# Supply_DDS.net
KiCad netlist of a schematic drawn in Altium Designer
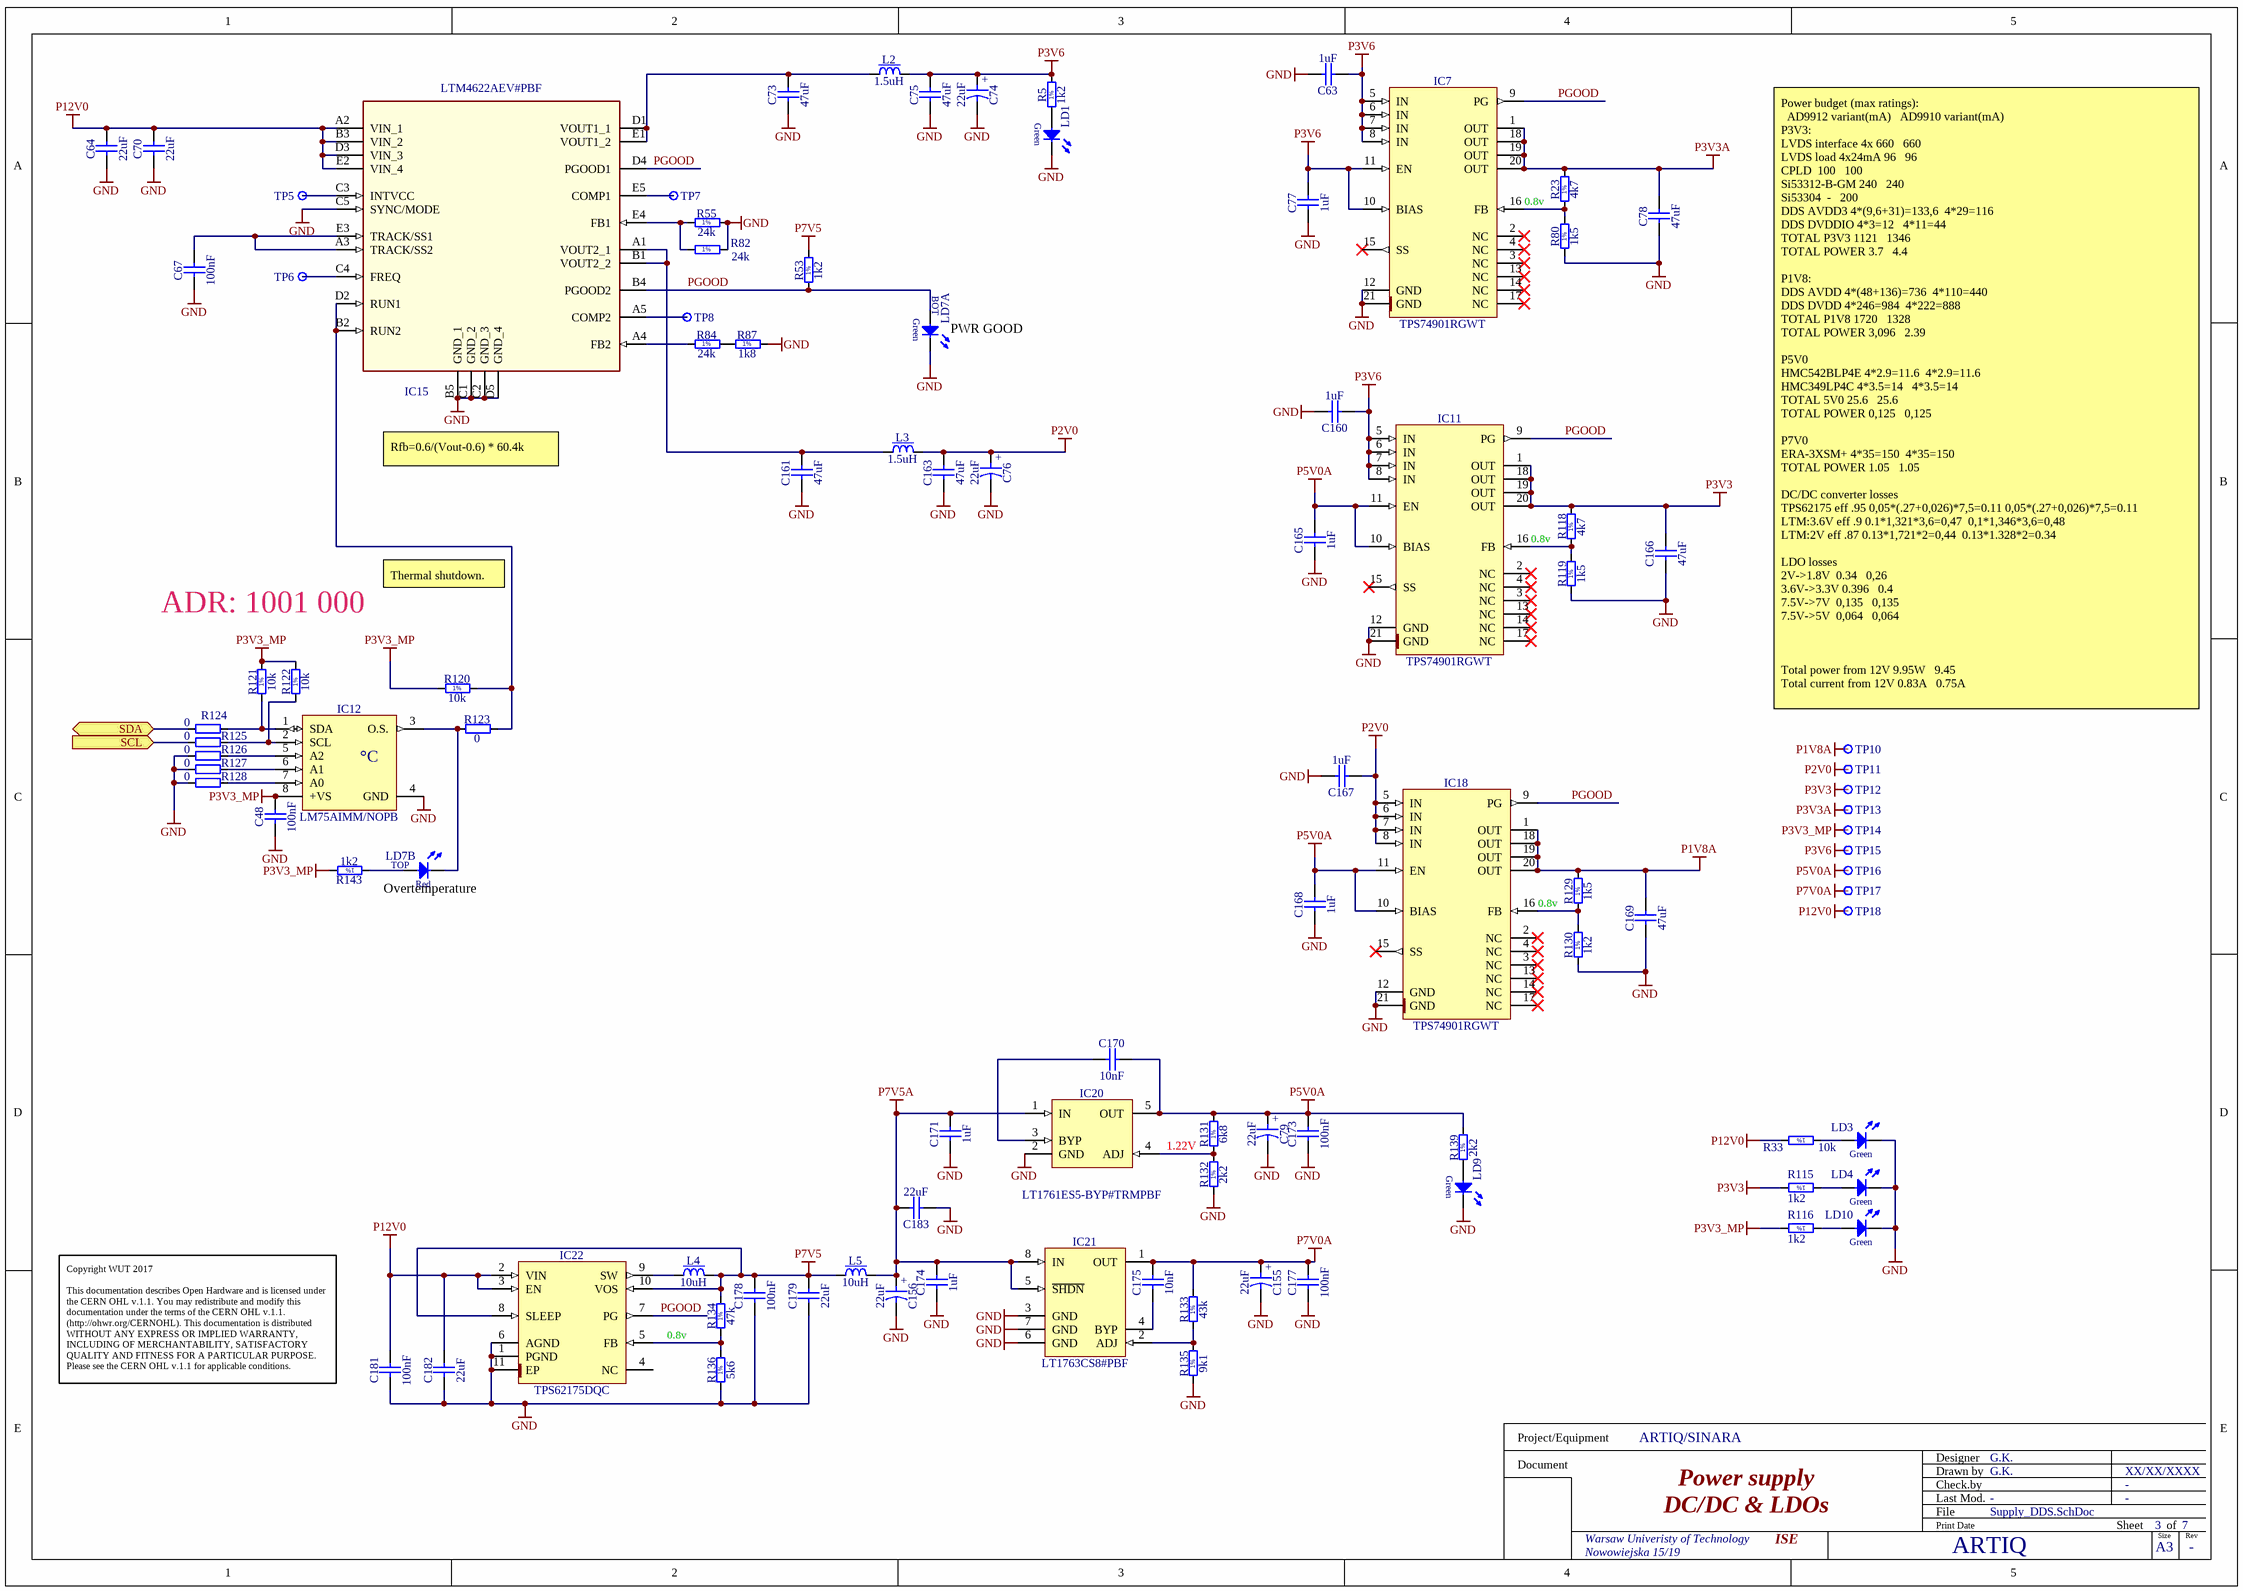
[diagram p0: Supply_DDS.SchDoc]

(export (version "E")
  (design (tool "Eeschema 10.0.6"))
  (components
    (comp (ref "C48")
      (value "100nF")
      (footprint "CAPC1005X55N")
      (description "Non-polarised capacitor")
      (fields (field (name "PART NUMBER") "CC0402_100NF_16V_10%_X5R") (field (name "VOLTAGE") "16V"))
      (libsource (lib "Capacitors") (part "Capacitor - non polarized"))
    )
    (comp (ref "C63")
      (value "1uF")
      (footprint "CAPC1005X55N")
      (description "Non-polarised capacitor")
      (fields (field (name "PART NUMBER") "CC0402_1UF_16V_10%_X5R") (field (name "VOLTAGE") "16V"))
      (libsource (lib "Capacitors") (part "Capacitor - non polarized"))
    )
    (comp (ref "C64")
      (value "22uF")
      (footprint "CAPC2012X135N")
      (description "Non-polarised capacitor")
      (fields (field (name "PART NUMBER") "CC0805_22UF_16V_10%_X5R") (field (name "VOLTAGE") "16V"))
      (libsource (lib "Capacitors") (part "Capacitor - non polarized"))
    )
    (comp (ref "C67")
      (value "100nF")
      (footprint "CAPC1005X55N")
      (description "Non-polarised capacitor")
      (fields (field (name "PART NUMBER") "CC0402_100NF_16V_10%_X5R") (field (name "VOLTAGE") "16V"))
      (libsource (lib "Capacitors") (part "Capacitor - non polarized"))
    )
    (comp (ref "C70")
      (value "22uF")
      (footprint "CAPC2012X135N")
      (description "Non-polarised capacitor")
      (fields (field (name "PART NUMBER") "CC0805_22UF_16V_10%_X5R") (field (name "VOLTAGE") "16V"))
      (libsource (lib "Capacitors") (part "Capacitor - non polarized"))
    )
    (comp (ref "C73")
      (value "47uF")
      (footprint "CAPC3225X270N")
      (description "Non-polarised capacitor")
      (fields (field (name "PART NUMBER") "CC1210_47UF_10V_20%_X5R") (field (name "VOLTAGE") "10V"))
      (libsource (lib "Capacitors") (part "Capacitor - non polarized"))
    )
    (comp (ref "C74")
      (value "22uF")
      (footprint "CAPMP3528X210N")
      (description "Polarised capacitor")
      (fields (field (name "PART NUMBER") "CTE3528-21_22UF_10V_10%_LESR0700") (field (name "VOLTAGE") "10V"))
      (libsource (lib "Capacitors") (part "Capacitor - polarized"))
    )
    (comp (ref "C75")
      (value "47uF")
      (footprint "CAPC3225X270N")
      (description "Non-polarised capacitor")
      (fields (field (name "PART NUMBER") "CC1210_47UF_10V_20%_X5R") (field (name "VOLTAGE") "10V"))
      (libsource (lib "Capacitors") (part "Capacitor - non polarized"))
    )
    (comp (ref "C76")
      (value "22uF")
      (footprint "CAPMP3528X210N")
      (description "Polarised capacitor")
      (fields (field (name "PART NUMBER") "CTE3528-21_22UF_10V_10%_LESR0700") (field (name "VOLTAGE") "10V"))
      (libsource (lib "Capacitors") (part "Capacitor - polarized"))
    )
    (comp (ref "C77")
      (value "1uF")
      (footprint "CAPC1005X55N")
      (description "Non-polarised capacitor")
      (fields (field (name "PART NUMBER") "CC0402_1UF_16V_10%_X5R") (field (name "VOLTAGE") "16V"))
      (libsource (lib "Capacitors") (part "Capacitor - non polarized"))
    )
    (comp (ref "C78")
      (value "47uF")
      (footprint "CAPC3225X270N")
      (description "Non-polarised capacitor")
      (fields (field (name "PART NUMBER") "CC1210_47UF_10V_20%_X5R") (field (name "VOLTAGE") "10V"))
      (libsource (lib "Capacitors") (part "Capacitor - non polarized"))
    )
    (comp (ref "C79")
      (value "22uF")
      (footprint "CAPMP3528X210N")
      (description "Polarised capacitor")
      (fields (field (name "PART NUMBER") "CTE3528-21_22UF_10V_10%_LESR0700") (field (name "VOLTAGE") "10V"))
      (libsource (lib "Capacitors") (part "Capacitor - polarized"))
    )
    (comp (ref "C155")
      (value "22uF")
      (footprint "CAPMP3528X210N")
      (description "Polarised capacitor")
      (fields (field (name "PART NUMBER") "CTE3528-21_22UF_10V_10%_LESR0700") (field (name "VOLTAGE") "10V"))
      (libsource (lib "Capacitors") (part "Capacitor - polarized"))
    )
    (comp (ref "C156")
      (value "22uF")
      (footprint "CAPMP3528X210N")
      (description "Polarised capacitor")
      (fields (field (name "PART NUMBER") "CTE3528-21_22UF_10V_10%_LESR0700") (field (name "VOLTAGE") "10V"))
      (libsource (lib "Capacitors") (part "Capacitor - polarized"))
    )
    (comp (ref "C160")
      (value "1uF")
      (footprint "CAPC1005X55N")
      (description "Non-polarised capacitor")
      (fields (field (name "PART NUMBER") "CC0402_1UF_16V_10%_X5R") (field (name "VOLTAGE") "16V"))
      (libsource (lib "Capacitors") (part "Capacitor - non polarized"))
    )
    (comp (ref "C161")
      (value "47uF")
      (footprint "CAPC3225X270N")
      (description "Non-polarised capacitor")
      (fields (field (name "PART NUMBER") "CC1210_47UF_10V_20%_X5R") (field (name "VOLTAGE") "10V"))
      (libsource (lib "Capacitors") (part "Capacitor - non polarized"))
    )
    (comp (ref "C163")
      (value "47uF")
      (footprint "CAPC3225X270N")
      (description "Non-polarised capacitor")
      (fields (field (name "PART NUMBER") "CC1210_47UF_10V_20%_X5R") (field (name "VOLTAGE") "10V"))
      (libsource (lib "Capacitors") (part "Capacitor - non polarized"))
    )
    (comp (ref "C165")
      (value "1uF")
      (footprint "CAPC1005X55N")
      (description "Non-polarised capacitor")
      (fields (field (name "PART NUMBER") "CC0402_1UF_16V_10%_X5R") (field (name "VOLTAGE") "16V"))
      (libsource (lib "Capacitors") (part "Capacitor - non polarized"))
    )
    (comp (ref "C166")
      (value "47uF")
      (footprint "CAPC3225X270N")
      (description "Non-polarised capacitor")
      (fields (field (name "PART NUMBER") "CC1210_47UF_10V_20%_X5R") (field (name "VOLTAGE") "10V"))
      (libsource (lib "Capacitors") (part "Capacitor - non polarized"))
    )
    (comp (ref "C167")
      (value "1uF")
      (footprint "CAPC1005X55N")
      (description "Non-polarised capacitor")
      (fields (field (name "PART NUMBER") "CC0402_1UF_16V_10%_X5R") (field (name "VOLTAGE") "16V"))
      (libsource (lib "Capacitors") (part "Capacitor - non polarized"))
    )
    (comp (ref "C168")
      (value "1uF")
      (footprint "CAPC1005X55N")
      (description "Non-polarised capacitor")
      (fields (field (name "PART NUMBER") "CC0402_1UF_16V_10%_X5R") (field (name "VOLTAGE") "16V"))
      (libsource (lib "Capacitors") (part "Capacitor - non polarized"))
    )
    (comp (ref "C169")
      (value "47uF")
      (footprint "CAPC3225X270N")
      (description "Non-polarised capacitor")
      (fields (field (name "PART NUMBER") "CC1210_47UF_10V_20%_X5R") (field (name "VOLTAGE") "10V"))
      (libsource (lib "Capacitors") (part "Capacitor - non polarized"))
    )
    (comp (ref "C170")
      (value "10nF")
      (footprint "CAPC1005X55N")
      (description "Non-polarised capacitor")
      (fields (field (name "PART NUMBER") "CC0402_10NF_16V_10%_X7R") (field (name "VOLTAGE") "16V"))
      (libsource (lib "Capacitors") (part "Capacitor - non polarized"))
    )
    (comp (ref "C171")
      (value "1uF")
      (footprint "CAPC1005X55N")
      (description "Non-polarised capacitor")
      (fields (field (name "PART NUMBER") "CC0402_1UF_16V_10%_X5R") (field (name "VOLTAGE") "16V"))
      (libsource (lib "Capacitors") (part "Capacitor - non polarized"))
    )
    (comp (ref "C173")
      (value "100nF")
      (footprint "CAPC1005X55N")
      (description "Non-polarised capacitor")
      (fields (field (name "PART NUMBER") "CC0402_100NF_16V_10%_X5R") (field (name "VOLTAGE") "16V"))
      (libsource (lib "Capacitors") (part "Capacitor - non polarized"))
    )
    (comp (ref "C174")
      (value "1uF")
      (footprint "CAPC1005X55N")
      (description "Non-polarised capacitor")
      (fields (field (name "PART NUMBER") "CC0402_1UF_16V_10%_X5R") (field (name "VOLTAGE") "16V"))
      (libsource (lib "Capacitors") (part "Capacitor - non polarized"))
    )
    (comp (ref "C175")
      (value "10nF")
      (footprint "CAPC1005X55N")
      (description "Non-polarised capacitor")
      (fields (field (name "PART NUMBER") "CC0402_10NF_16V_10%_X7R") (field (name "VOLTAGE") "16V"))
      (libsource (lib "Capacitors") (part "Capacitor - non polarized"))
    )
    (comp (ref "C177")
      (value "100nF")
      (footprint "CAPC1005X55N")
      (description "Non-polarised capacitor")
      (fields (field (name "PART NUMBER") "CC0402_100NF_16V_10%_X5R") (field (name "VOLTAGE") "16V"))
      (libsource (lib "Capacitors") (part "Capacitor - non polarized"))
    )
    (comp (ref "C178")
      (value "100nF")
      (footprint "CAPC1005X55N")
      (description "Non-polarised capacitor")
      (fields (field (name "PART NUMBER") "CC0402_100NF_16V_10%_X5R") (field (name "VOLTAGE") "16V"))
      (libsource (lib "Capacitors") (part "Capacitor - non polarized"))
    )
    (comp (ref "C179")
      (value "22uF")
      (footprint "CAPC2012X135N")
      (description "Non-polarised capacitor")
      (fields (field (name "PART NUMBER") "CC0805_22UF_16V_10%_X5R") (field (name "VOLTAGE") "16V"))
      (libsource (lib "Capacitors") (part "Capacitor - non polarized"))
    )
    (comp (ref "C181")
      (value "100nF")
      (footprint "CAPC1005X55N")
      (description "Non-polarised capacitor")
      (fields (field (name "PART NUMBER") "CC0402_100NF_16V_10%_X5R") (field (name "VOLTAGE") "16V"))
      (libsource (lib "Capacitors") (part "Capacitor - non polarized"))
    )
    (comp (ref "C182")
      (value "22uF")
      (footprint "CAPC2012X135N")
      (description "Non-polarised capacitor")
      (fields (field (name "PART NUMBER") "CC0805_22UF_16V_10%_X5R") (field (name "VOLTAGE") "16V"))
      (libsource (lib "Capacitors") (part "Capacitor - non polarized"))
    )
    (comp (ref "C183")
      (value "22uF")
      (footprint "CAPC2012X135N")
      (description "Non-polarised capacitor")
      (fields (field (name "PART NUMBER") "CC0805_22UF_16V_10%_X5R") (field (name "VOLTAGE") "16V"))
      (libsource (lib "Capacitors") (part "Capacitor - non polarized"))
    )
    (comp (ref "IC7")
      (value "TPS74901RGWT")
      (footprint "QFN65P500X500X100-21N-S325")
      (description "3A, 0.8 to 3.6V Adjustable Low-Dropout Linear Regulator with Programmable Soft-Start")
      (fields (field (name "MANUFACTURER") "TEXAS INSTRUMENTS"))
      (libsource (lib "ICs And Semiconductors") (part "TPS74901RGWT"))
    )
    (comp (ref "IC11")
      (value "TPS74901RGWT")
      (footprint "QFN65P500X500X100-21N-S325")
      (description "3A, 0.8 to 3.6V Adjustable Low-Dropout Linear Regulator with Programmable Soft-Start")
      (fields (field (name "MANUFACTURER") "TEXAS INSTRUMENTS"))
      (libsource (lib "ICs And Semiconductors") (part "TPS74901RGWT"))
    )
    (comp (ref "IC12")
      (value "LM75AIMM/NOPB")
      (footprint "SOP65P490X109-8N")
      (description "Digital Temperature Sensor and Thermal Watchdog with Two-Wire Interface")
      (fields (field (name "MANUFACTURER") "TEXAS INSTRUMENTS"))
      (libsource (lib "ICs And Semiconductors") (part "LM75"))
    )
    (comp (ref "IC15")
      (value "LTM4622AEV#PBF")
      (footprint "LGA25C127P5X5_625X625X190")
      (description "Dual Ultrathin 2A or Single 4A, 3.6V to 20V, 1.5V to 12V   Step-Down DC/DC μModule Regulator")
      (fields (field (name "MANUFACTURER") "LINEAR TECHNOLOGY"))
      (libsource (lib "LIBRARY_SCH") (part "PM_LTM4622"))
    )
    (comp (ref "IC18")
      (value "TPS74901RGWT")
      (footprint "QFN65P500X500X100-21N-S325")
      (description "3A, 0.8 to 3.6V Adjustable Low-Dropout Linear Regulator with Programmable Soft-Start")
      (fields (field (name "MANUFACTURER") "TEXAS INSTRUMENTS"))
      (libsource (lib "ICs And Semiconductors") (part "TPS74901RGWT"))
    )
    (comp (ref "IC20")
      (value "LT1761ES5-BYP#TRMPBF")
      (footprint "SOT95P280X100-5N")
      (description "100mA, Low Noise, LDO Micropower Adjustable Regulator in SOT-23")
      (fields (field (name "MANUFACTURER") "LINEAR TECHNOLOGY"))
      (libsource (lib "ICs And Semiconductors") (part "LT1761-BYP"))
    )
    (comp (ref "IC21")
      (value "LT1763CS8#PBF")
      (footprint "SOIC127P600X175-8N")
      (description "1.22V to 20V 500mA, Low Noise, LDO Adjustable Micropower Regulator")
      (fields (field (name "MANUFACTURER") "LINEAR TECHNOLOGY"))
      (libsource (lib "ICs And Semiconductors") (part "LT1763xS8"))
    )
    (comp (ref "IC22")
      (value "TPS62175DQC")
      (footprint "SON50P200X300X80-11N-R94X250")
      (description "4.75-28VDC to 1-6VDC, 500mA Step-Down Converter With Sleep Mode")
      (fields (field (name "MANUFACTURER") "TEXAS INSTRUMENTS"))
      (libsource (lib "ICs And Semiconductors") (part "TPS62175"))
    )
    (comp (ref "L2")
      (value "1.5uH")
      (footprint "IND_TDK_SPM6530")
      (description "Inductor With Core")
      (fields (field (name "PART NUMBER") "IND_1.5UH_20%_TDK_SPM6530") (field (name "POWER") "11A"))
      (libsource (lib "Inductors & Transformers") (part "Inductor With Magnetic core"))
    )
    (comp (ref "L3")
      (value "1.5uH")
      (footprint "IND_TDK_SPM6530")
      (description "Inductor With Core")
      (fields (field (name "PART NUMBER") "IND_1.5UH_20%_TDK_SPM6530") (field (name "POWER") "11A"))
      (libsource (lib "Inductors & Transformers") (part "Inductor With Magnetic core"))
    )
    (comp (ref "L4")
      (value "10uH")
      (footprint "IND_MURATA-PS_8400")
      (description "Inductor With Core")
      (fields (field (name "PART NUMBER") "IND_10UH_10%_MURATA-PS_8400") (field (name "POWER") "950mA"))
      (libsource (lib "Inductors & Transformers") (part "Inductor With Magnetic core"))
    )
    (comp (ref "L5")
      (value "10uH")
      (footprint "IND_MURATA-PS_8400")
      (description "Inductor With Core")
      (fields (field (name "PART NUMBER") "IND_10UH_10%_MURATA-PS_8400") (field (name "POWER") "950mA"))
      (libsource (lib "Inductors & Transformers") (part "Inductor With Magnetic core"))
    )
    (comp (ref "LD1")
      (value "Green")
      (footprint "LED_KINGBRIGHT_KPH-1608CGCKr")
      (description "Green 0603")
      (fields
        (field (name "PART NUMBER") "LED_KINGBRIGHT_KPH-1608CGCK")
        (field (name "MANUFACTURER") "KINGBRIGHT")
      )
      (libsource (lib "LIBRARY_SCH") (part "LED_0603_Green"))
    )
    (comp (ref "LD3")
      (value "Green")
      (footprint "LED_KINGBRIGHT_KPH-1608CGCKr")
      (description "Green 0603")
      (fields
        (field (name "PART NUMBER") "LED_KINGBRIGHT_KPH-1608CGCK")
        (field (name "MANUFACTURER") "KINGBRIGHT")
      )
      (libsource (lib "LIBRARY_SCH") (part "LED_0603_Green"))
    )
    (comp (ref "LD4")
      (value "Green")
      (footprint "LED_KINGBRIGHT_KPH-1608CGCKr")
      (description "Green 0603")
      (fields
        (field (name "PART NUMBER") "LED_KINGBRIGHT_KPH-1608CGCK")
        (field (name "MANUFACTURER") "KINGBRIGHT")
      )
      (libsource (lib "LIBRARY_SCH") (part "LED_0603_Green"))
    )
    (comp (ref "LD7")
      (value "Red/Green")
      (footprint "LED_DIALIGHT_553-0112-200F")
      (description "2x LED  Botom Green, Top Red")
      (fields
        (field (name "PART NUMBER") "LED_DIALIGHT_553-0112-200F")
        (field (name "MANUFACTURER") "DIALIGHT")
      )
      (libsource (lib "ICs And Semiconductors") (part "LED x2 G-1C2A-BOT_R-3C4A-TOP"))
    )
    (comp (ref "LD9")
      (value "Green")
      (footprint "LED_KINGBRIGHT_KPH-1608CGCKr")
      (description "Green 0603")
      (fields
        (field (name "PART NUMBER") "LED_KINGBRIGHT_KPH-1608CGCK")
        (field (name "MANUFACTURER") "KINGBRIGHT")
      )
      (libsource (lib "LIBRARY_SCH") (part "LED_0603_Green"))
    )
    (comp (ref "LD10")
      (value "Green")
      (footprint "LED_KINGBRIGHT_KPH-1608CGCKr")
      (description "Green 0603")
      (fields
        (field (name "PART NUMBER") "LED_KINGBRIGHT_KPH-1608CGCK")
        (field (name "MANUFACTURER") "KINGBRIGHT")
      )
      (libsource (lib "LIBRARY_SCH") (part "LED_0603_Green"))
    )
    (comp (ref "R5")
      (value "1k2")
      (footprint "RESC1608X55N")
      (description "Resistor - 1%")
      (fields (field (name "PART NUMBER") "R0603_1K2_1%_0.1W_100PPM") (field (name "POWER") "0.1W"))
      (libsource (lib "Resistors") (part "Resistor - 1%"))
    )
    (comp (ref "R23")
      (value "4k7")
      (footprint "RESC1608X55N")
      (description "Resistor - 1%")
      (fields (field (name "PART NUMBER") "R0603_4K7_1%_0.1W_100PPM") (field (name "POWER") "0.1W"))
      (libsource (lib "Resistors") (part "Resistor - 1%"))
    )
    (comp (ref "R33")
      (value "10k")
      (footprint "RESC1005X40N")
      (description "Resistor - 1%")
      (fields (field (name "PART NUMBER") "R0402_10K_1%_0.0625W_100PPM") (field (name "POWER") "0.0625W"))
      (libsource (lib "Resistors") (part "Resistor - 1%"))
    )
    (comp (ref "R53")
      (value "1k2")
      (footprint "RESC1608X55N")
      (description "Resistor - 1%")
      (fields (field (name "PART NUMBER") "R0603_1K2_1%_0.1W_100PPM") (field (name "POWER") "0.1W"))
      (libsource (lib "Resistors") (part "Resistor - 1%"))
    )
    (comp (ref "R55")
      (value "24k")
      (footprint "RESC1608X55N")
      (description "Resistor - 1%")
      (fields (field (name "PART NUMBER") "R0603_24K_1%_0.1W_100PPM") (field (name "POWER") "0.1W"))
      (libsource (lib "Resistors") (part "Resistor - 1%"))
    )
    (comp (ref "R80")
      (value "1k5")
      (footprint "RESC1608X55N")
      (description "Resistor - 1%")
      (fields (field (name "PART NUMBER") "R0603_1K5_1%_0.1W_100PPM") (field (name "POWER") "0.1W"))
      (libsource (lib "Resistors") (part "Resistor - 1%"))
    )
    (comp (ref "R82")
      (value "24k")
      (footprint "RESC1608X55N")
      (description "Resistor - 1%")
      (fields (field (name "PART NUMBER") "R0603_24K_1%_0.1W_100PPM") (field (name "POWER") "0.1W"))
      (libsource (lib "Resistors") (part "Resistor - 1%"))
    )
    (comp (ref "R84")
      (value "24k")
      (footprint "RESC1608X55N")
      (description "Resistor - 1%")
      (fields (field (name "PART NUMBER") "R0603_24K_1%_0.1W_100PPM") (field (name "POWER") "0.1W"))
      (libsource (lib "Resistors") (part "Resistor - 1%"))
    )
    (comp (ref "R87")
      (value "1k8")
      (footprint "RESC1608X55N")
      (description "Resistor - 1%")
      (fields (field (name "PART NUMBER") "R0603_1K8_1%_0.1W_100PPM") (field (name "POWER") "0.1W"))
      (libsource (lib "Resistors") (part "Resistor - 1%"))
    )
    (comp (ref "R115")
      (value "1k2")
      (footprint "RESC1608X55N")
      (description "Resistor - 1%")
      (fields (field (name "PART NUMBER") "R0603_1K2_1%_0.1W_100PPM") (field (name "POWER") "0.1W"))
      (libsource (lib "Resistors") (part "Resistor - 1%"))
    )
    (comp (ref "R116")
      (value "1k2")
      (footprint "RESC1608X55N")
      (description "Resistor - 1%")
      (fields (field (name "PART NUMBER") "R0603_1K2_1%_0.1W_100PPM") (field (name "POWER") "0.1W"))
      (libsource (lib "Resistors") (part "Resistor - 1%"))
    )
    (comp (ref "R118")
      (value "4k7")
      (footprint "RESC1608X55N")
      (description "Resistor - 1%")
      (fields (field (name "PART NUMBER") "R0603_4K7_1%_0.1W_100PPM") (field (name "POWER") "0.1W"))
      (libsource (lib "Resistors") (part "Resistor - 1%"))
    )
    (comp (ref "R119")
      (value "1k5")
      (footprint "RESC1608X55N")
      (description "Resistor - 1%")
      (fields (field (name "PART NUMBER") "R0603_1K5_1%_0.1W_100PPM") (field (name "POWER") "0.1W"))
      (libsource (lib "Resistors") (part "Resistor - 1%"))
    )
    (comp (ref "R120")
      (value "10k")
      (footprint "RESC1005X40N")
      (description "Resistor - 1%")
      (fields (field (name "PART NUMBER") "R0402_10K_1%_0.0625W_100PPM") (field (name "POWER") "0.0625W"))
      (libsource (lib "Resistors") (part "Resistor - 1%"))
    )
    (comp (ref "R121")
      (value "10k")
      (footprint "RESC1005X40N")
      (description "Resistor - 1%")
      (fields (field (name "PART NUMBER") "R0402_10K_1%_0.0625W_100PPM") (field (name "POWER") "0.0625W"))
      (libsource (lib "Resistors") (part "Resistor - 1%"))
    )
    (comp (ref "R122")
      (value "10k")
      (footprint "RESC1005X40N")
      (description "Resistor - 1%")
      (fields (field (name "PART NUMBER") "R0402_10K_1%_0.0625W_100PPM") (field (name "POWER") "0.0625W"))
      (libsource (lib "Resistors") (part "Resistor - 1%"))
    )
    (comp (ref "R123")
      (value "0")
      (footprint "RESC1005X40N")
      (description "Resistor")
      (fields (field (name "PART NUMBER") "R0402_0R_JUMPER") (field (name "MANUFACTURER") "GENERIC"))
      (libsource (lib "Resistors") (part "Resistor"))
    )
    (comp (ref "R124")
      (value "0")
      (footprint "RESC1005X40N")
      (description "Resistor")
      (fields (field (name "PART NUMBER") "R0402_0R_JUMPER") (field (name "MANUFACTURER") "GENERIC"))
      (libsource (lib "Resistors") (part "Resistor"))
    )
    (comp (ref "R125")
      (value "0")
      (footprint "RESC1005X40N")
      (description "Resistor")
      (fields (field (name "PART NUMBER") "R0402_0R_JUMPER") (field (name "MANUFACTURER") "GENERIC"))
      (libsource (lib "Resistors") (part "Resistor"))
    )
    (comp (ref "R126")
      (value "0")
      (footprint "RESC1005X40N")
      (description "Resistor")
      (fields (field (name "PART NUMBER") "R0402_0R_JUMPER") (field (name "MANUFACTURER") "GENERIC"))
      (libsource (lib "Resistors") (part "Resistor"))
    )
    (comp (ref "R127")
      (value "0")
      (footprint "RESC1005X40N")
      (description "Resistor")
      (fields (field (name "PART NUMBER") "R0402_0R_JUMPER") (field (name "MANUFACTURER") "GENERIC"))
      (libsource (lib "Resistors") (part "Resistor"))
    )
    (comp (ref "R128")
      (value "0")
      (footprint "RESC1005X40N")
      (description "Resistor")
      (fields (field (name "PART NUMBER") "R0402_0R_JUMPER") (field (name "MANUFACTURER") "GENERIC"))
      (libsource (lib "Resistors") (part "Resistor"))
    )
    (comp (ref "R129")
      (value "1k5")
      (footprint "RESC1608X55N")
      (description "Resistor - 1%")
      (fields (field (name "PART NUMBER") "R0603_1K5_1%_0.1W_100PPM") (field (name "POWER") "0.1W"))
      (libsource (lib "Resistors") (part "Resistor - 1%"))
    )
    (comp (ref "R130")
      (value "1k2")
      (footprint "RESC1608X55N")
      (description "Resistor - 1%")
      (fields (field (name "PART NUMBER") "R0603_1K2_1%_0.1W_100PPM") (field (name "POWER") "0.1W"))
      (libsource (lib "Resistors") (part "Resistor - 1%"))
    )
    (comp (ref "R131")
      (value "6k8")
      (footprint "RESC1608X55N")
      (description "Resistor - 1%")
      (fields (field (name "PART NUMBER") "R0603_6K8_1%_0.1W_100PPM") (field (name "POWER") "0.1W"))
      (libsource (lib "Resistors") (part "Resistor - 1%"))
    )
    (comp (ref "R132")
      (value "2k2")
      (footprint "RESC1608X55N")
      (description "Resistor - 1%")
      (fields (field (name "PART NUMBER") "R0603_2K2_1%_0.1W_100PPM") (field (name "POWER") "0.1W"))
      (libsource (lib "Resistors") (part "Resistor - 1%"))
    )
    (comp (ref "R133")
      (value "43k")
      (footprint "RESC1608X55N")
      (description "Resistor - 1%")
      (fields (field (name "PART NUMBER") "R0603_43K_1%_0.1W_100PPM") (field (name "POWER") "0.1W"))
      (libsource (lib "Resistors") (part "Resistor - 1%"))
    )
    (comp (ref "R134")
      (value "47k")
      (footprint "RESC1608X55N")
      (description "Resistor - 1%")
      (fields (field (name "PART NUMBER") "R0603_47K_1%_0.1W_100PPM") (field (name "POWER") "0.1W"))
      (libsource (lib "Resistors") (part "Resistor - 1%"))
    )
    (comp (ref "R135")
      (value "9k1")
      (footprint "RESC1608X55N")
      (description "Resistor - 1%")
      (fields (field (name "PART NUMBER") "R0603_9K1_1%_0.1W_100PPM") (field (name "POWER") "0.1W"))
      (libsource (lib "Resistors") (part "Resistor - 1%"))
    )
    (comp (ref "R136")
      (value "5k6")
      (footprint "RESC1608X55N")
      (description "Resistor - 1%")
      (fields (field (name "PART NUMBER") "R0603_5K6_1%_0.1W_100PPM") (field (name "POWER") "0.1W"))
      (libsource (lib "Resistors") (part "Resistor - 1%"))
    )
    (comp (ref "R139")
      (value "2k2")
      (footprint "RESC1608X55N")
      (description "Resistor - 1%")
      (fields (field (name "PART NUMBER") "R0603_2K2_1%_0.1W_100PPM") (field (name "POWER") "0.1W"))
      (libsource (lib "Resistors") (part "Resistor - 1%"))
    )
    (comp (ref "R143")
      (value "1k2")
      (footprint "RESC1608X55N")
      (description "Resistor - 1%")
      (fields (field (name "PART NUMBER") "R0603_1K2_1%_0.1W_100PPM") (field (name "POWER") "0.1W"))
      (libsource (lib "Resistors") (part "Resistor - 1%"))
    )
    (comp (ref "TP5")
      (value "Test Point")
      (footprint "TPS127")
      (fields (field (name "PART NUMBER") "SMD_PAD_1.27X1.27MM"))
      (libsource (lib "Eletro-mechanical") (part "Test Point"))
    )
    (comp (ref "TP6")
      (value "Test Point")
      (footprint "TPS127")
      (fields (field (name "PART NUMBER") "SMD_PAD_1.27X1.27MM"))
      (libsource (lib "Eletro-mechanical") (part "Test Point"))
    )
    (comp (ref "TP7")
      (value "Test Point")
      (footprint "TPS127")
      (fields (field (name "PART NUMBER") "SMD_PAD_1.27X1.27MM"))
      (libsource (lib "Eletro-mechanical") (part "Test Point"))
    )
    (comp (ref "TP8")
      (value "Test Point")
      (footprint "TPS127")
      (fields (field (name "PART NUMBER") "SMD_PAD_1.27X1.27MM"))
      (libsource (lib "Eletro-mechanical") (part "Test Point"))
    )
    (comp (ref "TP10")
      (value "Test Point")
      (footprint "TPS127")
      (fields (field (name "PART NUMBER") "SMD_PAD_1.27X1.27MM"))
      (libsource (lib "Eletro-mechanical") (part "Test Point"))
    )
    (comp (ref "TP11")
      (value "Test Point")
      (footprint "TPS127")
      (fields (field (name "PART NUMBER") "SMD_PAD_1.27X1.27MM"))
      (libsource (lib "Eletro-mechanical") (part "Test Point"))
    )
    (comp (ref "TP12")
      (value "Test Point")
      (footprint "TPS127")
      (fields (field (name "PART NUMBER") "SMD_PAD_1.27X1.27MM"))
      (libsource (lib "Eletro-mechanical") (part "Test Point"))
    )
    (comp (ref "TP13")
      (value "Test Point")
      (footprint "TPS127")
      (fields (field (name "PART NUMBER") "SMD_PAD_1.27X1.27MM"))
      (libsource (lib "Eletro-mechanical") (part "Test Point"))
    )
    (comp (ref "TP14")
      (value "Test Point")
      (footprint "TPS127")
      (fields (field (name "PART NUMBER") "SMD_PAD_1.27X1.27MM"))
      (libsource (lib "Eletro-mechanical") (part "Test Point"))
    )
    (comp (ref "TP15")
      (value "Test Point")
      (footprint "TPS127")
      (fields (field (name "PART NUMBER") "SMD_PAD_1.27X1.27MM"))
      (libsource (lib "Eletro-mechanical") (part "Test Point"))
    )
    (comp (ref "TP16")
      (value "Test Point")
      (footprint "TPS127")
      (fields (field (name "PART NUMBER") "SMD_PAD_1.27X1.27MM"))
      (libsource (lib "Eletro-mechanical") (part "Test Point"))
    )
    (comp (ref "TP17")
      (value "Test Point")
      (footprint "TPS127")
      (fields (field (name "PART NUMBER") "SMD_PAD_1.27X1.27MM"))
      (libsource (lib "Eletro-mechanical") (part "Test Point"))
    )
    (comp (ref "TP18")
      (value "Test Point")
      (footprint "TPS127")
      (fields (field (name "PART NUMBER") "SMD_PAD_1.27X1.27MM"))
      (libsource (lib "Eletro-mechanical") (part "Test Point"))
    )
  )
  (nets
    (net (code "1") (name "/PGOOD") (class "Default")
      (node (ref "IC11") (pin "9") (pinfunction "PG_9") (pintype "output"))
      (node (ref "IC15") (pin "B4") (pinfunction "PGOOD2_B4") (pintype "open_collector"))
      (node (ref "IC15") (pin "D4") (pinfunction "PGOOD1_D4") (pintype "open_collector"))
      (node (ref "IC18") (pin "9") (pinfunction "PG_9") (pintype "output"))
      (node (ref "IC22") (pin "7") (pinfunction "PG_7") (pintype "output"))
      (node (ref "IC7") (pin "9") (pinfunction "PG_9") (pintype "output"))
      (node (ref "LD7") (pin "2") (pinfunction "A_2") (pintype "passive"))
      (node (ref "R53") (pin "1") (pinfunction "1_1") (pintype "passive"))
    )
    (net (code "2") (name "/SCL") (class "Default")
      (node (ref "R125") (pin "1") (pinfunction "1_1") (pintype "passive"))
    )
    (net (code "3") (name "/SDA") (class "Default")
      (node (ref "R124") (pin "1") (pinfunction "1_1") (pintype "passive"))
    )
    (net (code "4") (name "GND") (class "Default")
      (node (ref "C155") (pin "2") (pinfunction "2_2") (pintype "passive"))
      (node (ref "C156") (pin "2") (pinfunction "2_2") (pintype "passive"))
      (node (ref "C160") (pin "2") (pinfunction "2_2") (pintype "passive"))
      (node (ref "C161") (pin "1") (pinfunction "1_1") (pintype "passive"))
      (node (ref "C163") (pin "1") (pinfunction "1_1") (pintype "passive"))
      (node (ref "C165") (pin "1") (pinfunction "1_1") (pintype "passive"))
      (node (ref "C166") (pin "1") (pinfunction "1_1") (pintype "passive"))
      (node (ref "C167") (pin "2") (pinfunction "2_2") (pintype "passive"))
      (node (ref "C168") (pin "1") (pinfunction "1_1") (pintype "passive"))
      (node (ref "C169") (pin "1") (pinfunction "1_1") (pintype "passive"))
      (node (ref "C171") (pin "1") (pinfunction "1_1") (pintype "passive"))
      (node (ref "C173") (pin "1") (pinfunction "1_1") (pintype "passive"))
      (node (ref "C174") (pin "1") (pinfunction "1_1") (pintype "passive"))
      (node (ref "C177") (pin "1") (pinfunction "1_1") (pintype "passive"))
      (node (ref "C178") (pin "1") (pinfunction "1_1") (pintype "passive"))
      (node (ref "C179") (pin "1") (pinfunction "1_1") (pintype "passive"))
      (node (ref "C181") (pin "1") (pinfunction "1_1") (pintype "passive"))
      (node (ref "C182") (pin "1") (pinfunction "1_1") (pintype "passive"))
      (node (ref "C183") (pin "1") (pinfunction "1_1") (pintype "passive"))
      (node (ref "C48") (pin "1") (pinfunction "1_1") (pintype "passive"))
      (node (ref "C63") (pin "2") (pinfunction "2_2") (pintype "passive"))
      (node (ref "C64") (pin "1") (pinfunction "1_1") (pintype "passive"))
      (node (ref "C67") (pin "1") (pinfunction "1_1") (pintype "passive"))
      (node (ref "C70") (pin "1") (pinfunction "1_1") (pintype "passive"))
      (node (ref "C73") (pin "1") (pinfunction "1_1") (pintype "passive"))
      (node (ref "C74") (pin "2") (pinfunction "2_2") (pintype "passive"))
      (node (ref "C75") (pin "1") (pinfunction "1_1") (pintype "passive"))
      (node (ref "C76") (pin "2") (pinfunction "2_2") (pintype "passive"))
      (node (ref "C77") (pin "1") (pinfunction "1_1") (pintype "passive"))
      (node (ref "C78") (pin "1") (pinfunction "1_1") (pintype "passive"))
      (node (ref "C79") (pin "2") (pinfunction "2_2") (pintype "passive"))
      (node (ref "IC11") (pin "12") (pinfunction "GND_12") (pintype "power_in"))
      (node (ref "IC11") (pin "21") (pinfunction "GND_21") (pintype "power_in"))
      (node (ref "IC12") (pin "4") (pinfunction "GND_4") (pintype "power_in"))
      (node (ref "IC15") (pin "B5") (pinfunction "GND_1_B5") (pintype "power_in"))
      (node (ref "IC15") (pin "C1") (pinfunction "GND_2_C1") (pintype "power_in"))
      (node (ref "IC15") (pin "C2") (pinfunction "GND_3_C2") (pintype "power_in"))
      (node (ref "IC15") (pin "C5") (pinfunction "SYNC/MODE_C5") (pintype "input"))
      (node (ref "IC15") (pin "D5") (pinfunction "GND_4_D5") (pintype "power_in"))
      (node (ref "IC18") (pin "12") (pinfunction "GND_12") (pintype "power_in"))
      (node (ref "IC18") (pin "21") (pinfunction "GND_21") (pintype "power_in"))
      (node (ref "IC20") (pin "2") (pinfunction "GND_2") (pintype "power_in"))
      (node (ref "IC21") (pin "3") (pinfunction "GND_3") (pintype "power_in"))
      (node (ref "IC21") (pin "6") (pinfunction "GND_6") (pintype "power_in"))
      (node (ref "IC21") (pin "7") (pinfunction "GND_7") (pintype "power_in"))
      (node (ref "IC22") (pin "1") (pinfunction "PGND_1") (pintype "power_in"))
      (node (ref "IC22") (pin "11") (pinfunction "EP_11") (pintype "power_in"))
      (node (ref "IC22") (pin "6") (pinfunction "AGND_6") (pintype "power_in"))
      (node (ref "IC7") (pin "12") (pinfunction "GND_12") (pintype "power_in"))
      (node (ref "IC7") (pin "21") (pinfunction "GND_21") (pintype "power_in"))
      (node (ref "LD1") (pin "1") (pinfunction "C_1") (pintype "passive"))
      (node (ref "LD10") (pin "1") (pinfunction "C_1") (pintype "passive"))
      (node (ref "LD3") (pin "1") (pinfunction "C_1") (pintype "passive"))
      (node (ref "LD4") (pin "1") (pinfunction "C_1") (pintype "passive"))
      (node (ref "LD7") (pin "1") (pinfunction "C_1") (pintype "passive"))
      (node (ref "LD9") (pin "1") (pinfunction "C_1") (pintype "passive"))
      (node (ref "R119") (pin "1") (pinfunction "1_1") (pintype "passive"))
      (node (ref "R126") (pin "1") (pinfunction "1_1") (pintype "passive"))
      (node (ref "R127") (pin "1") (pinfunction "1_1") (pintype "passive"))
      (node (ref "R128") (pin "1") (pinfunction "1_1") (pintype "passive"))
      (node (ref "R130") (pin "1") (pinfunction "1_1") (pintype "passive"))
      (node (ref "R132") (pin "1") (pinfunction "1_1") (pintype "passive"))
      (node (ref "R135") (pin "1") (pinfunction "1_1") (pintype "passive"))
      (node (ref "R136") (pin "1") (pinfunction "1_1") (pintype "passive"))
      (node (ref "R55") (pin "2") (pinfunction "2_2") (pintype "passive"))
      (node (ref "R80") (pin "1") (pinfunction "1_1") (pintype "passive"))
      (node (ref "R82") (pin "2") (pinfunction "2_2") (pintype "passive"))
      (node (ref "R87") (pin "2") (pinfunction "2_2") (pintype "passive"))
    )
    (net (code "5") (name "Net-(IC7-FB)") (class "Default")
      (node (ref "IC7") (pin "16") (pinfunction "FB_16") (pintype "input"))
      (node (ref "R23") (pin "1") (pinfunction "1_1") (pintype "passive"))
      (node (ref "R80") (pin "2") (pinfunction "2_2") (pintype "passive"))
    )
    (net (code "6") (name "Net-(IC11-FB)") (class "Default")
      (node (ref "IC11") (pin "16") (pinfunction "FB_16") (pintype "input"))
      (node (ref "R118") (pin "1") (pinfunction "1_1") (pintype "passive"))
      (node (ref "R119") (pin "2") (pinfunction "2_2") (pintype "passive"))
    )
    (net (code "7") (name "Net-(IC12-A0)") (class "Default")
      (node (ref "IC12") (pin "7") (pinfunction "A0_7") (pintype "input"))
      (node (ref "R128") (pin "2") (pinfunction "2_2") (pintype "passive"))
    )
    (net (code "8") (name "Net-(IC12-A1)") (class "Default")
      (node (ref "IC12") (pin "6") (pinfunction "A1_6") (pintype "input"))
      (node (ref "R127") (pin "2") (pinfunction "2_2") (pintype "passive"))
    )
    (net (code "9") (name "Net-(IC12-A2)") (class "Default")
      (node (ref "IC12") (pin "5") (pinfunction "A2_5") (pintype "input"))
      (node (ref "R126") (pin "2") (pinfunction "2_2") (pintype "passive"))
    )
    (net (code "10") (name "Net-(IC12-O.S.)") (class "Default")
      (node (ref "IC12") (pin "3") (pinfunction "O.S._3") (pintype "output"))
      (node (ref "LD7") (pin "3") (pinfunction "C_3") (pintype "passive"))
      (node (ref "R123") (pin "1") (pinfunction "1_1") (pintype "passive"))
    )
    (net (code "11") (name "Net-(IC12-SCL)") (class "Default")
      (node (ref "IC12") (pin "2") (pinfunction "SCL_2") (pintype "input"))
      (node (ref "R122") (pin "1") (pinfunction "1_1") (pintype "passive"))
      (node (ref "R125") (pin "2") (pinfunction "2_2") (pintype "passive"))
    )
    (net (code "12") (name "Net-(IC12-SDA)") (class "Default")
      (node (ref "IC12") (pin "1") (pinfunction "SDA_1") (pintype "bidirectional"))
      (node (ref "R121") (pin "1") (pinfunction "1_1") (pintype "passive"))
      (node (ref "R124") (pin "2") (pinfunction "2_2") (pintype "passive"))
    )
    (net (code "13") (name "Net-(IC15-COMP1)") (class "Default")
      (node (ref "IC15") (pin "E5") (pinfunction "COMP1_E5") (pintype "passive"))
      (node (ref "TP7") (pin "1") (pinfunction "1_1") (pintype "bidirectional"))
    )
    (net (code "14") (name "Net-(IC15-COMP2)") (class "Default")
      (node (ref "IC15") (pin "A5") (pinfunction "COMP2_A5") (pintype "passive"))
      (node (ref "TP8") (pin "1") (pinfunction "1_1") (pintype "bidirectional"))
    )
    (net (code "15") (name "Net-(IC15-FB1)") (class "Default")
      (node (ref "IC15") (pin "E4") (pinfunction "FB1_E4") (pintype "input"))
      (node (ref "R55") (pin "1") (pinfunction "1_1") (pintype "passive"))
      (node (ref "R82") (pin "1") (pinfunction "1_1") (pintype "passive"))
    )
    (net (code "16") (name "Net-(IC15-FB2)") (class "Default")
      (node (ref "IC15") (pin "A4") (pinfunction "FB2_A4") (pintype "input"))
      (node (ref "R84") (pin "1") (pinfunction "1_1") (pintype "passive"))
    )
    (net (code "17") (name "Net-(IC15-FREQ)") (class "Default")
      (node (ref "IC15") (pin "C4") (pinfunction "FREQ_C4") (pintype "input"))
      (node (ref "TP6") (pin "1") (pinfunction "1_1") (pintype "bidirectional"))
    )
    (net (code "18") (name "Net-(IC15-INTVCC)") (class "Default")
      (node (ref "IC15") (pin "C3") (pinfunction "INTVCC_C3") (pintype "input"))
      (node (ref "TP5") (pin "1") (pinfunction "1_1") (pintype "bidirectional"))
    )
    (net (code "19") (name "Net-(IC15-RUN1)") (class "Default")
      (node (ref "IC15") (pin "B2") (pinfunction "RUN2_B2") (pintype "input"))
      (node (ref "IC15") (pin "D2") (pinfunction "RUN1_D2") (pintype "input"))
      (node (ref "R120") (pin "2") (pinfunction "2_2") (pintype "passive"))
      (node (ref "R123") (pin "2") (pinfunction "2_2") (pintype "passive"))
    )
    (net (code "20") (name "Net-(IC15-TRACK{slash}SS1)") (class "Default")
      (node (ref "C67") (pin "2") (pinfunction "2_2") (pintype "passive"))
      (node (ref "IC15") (pin "A3") (pinfunction "TRACK/SS2_A3") (pintype "input"))
      (node (ref "IC15") (pin "E3") (pinfunction "TRACK/SS1_E3") (pintype "input"))
    )
    (net (code "21") (name "Net-(IC15-VOUT1_1)") (class "Default")
      (node (ref "C73") (pin "2") (pinfunction "2_2") (pintype "passive"))
      (node (ref "IC15") (pin "D1") (pinfunction "VOUT1_1_D1") (pintype "power_in"))
      (node (ref "IC15") (pin "E1") (pinfunction "VOUT1_2_E1") (pintype "power_in"))
      (node (ref "L2") (pin "1") (pinfunction "1_1") (pintype "passive"))
    )
    (net (code "22") (name "Net-(IC15-VOUT2_1)") (class "Default")
      (node (ref "C161") (pin "2") (pinfunction "2_2") (pintype "passive"))
      (node (ref "IC15") (pin "A1") (pinfunction "VOUT2_1_A1") (pintype "power_in"))
      (node (ref "IC15") (pin "B1") (pinfunction "VOUT2_2_B1") (pintype "power_in"))
      (node (ref "L3") (pin "1") (pinfunction "1_1") (pintype "passive"))
    )
    (net (code "23") (name "Net-(IC18-FB)") (class "Default")
      (node (ref "IC18") (pin "16") (pinfunction "FB_16") (pintype "input"))
      (node (ref "R129") (pin "1") (pinfunction "1_1") (pintype "passive"))
      (node (ref "R130") (pin "2") (pinfunction "2_2") (pintype "passive"))
    )
    (net (code "24") (name "Net-(IC20-ADJ)") (class "Default")
      (node (ref "IC20") (pin "4") (pinfunction "ADJ_4") (pintype "input"))
      (node (ref "R131") (pin "1") (pinfunction "1_1") (pintype "passive"))
      (node (ref "R132") (pin "2") (pinfunction "2_2") (pintype "passive"))
    )
    (net (code "25") (name "Net-(IC20-BYP)") (class "Default")
      (node (ref "C170") (pin "1") (pinfunction "1_1") (pintype "passive"))
      (node (ref "IC20") (pin "3") (pinfunction "BYP_3") (pintype "input"))
    )
    (net (code "26") (name "Net-(IC21-ADJ)") (class "Default")
      (node (ref "IC21") (pin "2") (pinfunction "ADJ_2") (pintype "input"))
      (node (ref "R133") (pin "1") (pinfunction "1_1") (pintype "passive"))
      (node (ref "R135") (pin "2") (pinfunction "2_2") (pintype "passive"))
    )
    (net (code "27") (name "Net-(IC21-BYP)") (class "Default")
      (node (ref "C175") (pin "1") (pinfunction "1_1") (pintype "passive"))
      (node (ref "IC21") (pin "4") (pinfunction "BYP_4") (pintype "passive"))
    )
    (net (code "28") (name "Net-(IC22-FB)") (class "Default")
      (node (ref "IC22") (pin "5") (pinfunction "FB_5") (pintype "input"))
      (node (ref "R134") (pin "1") (pinfunction "1_1") (pintype "passive"))
      (node (ref "R136") (pin "2") (pinfunction "2_2") (pintype "passive"))
    )
    (net (code "29") (name "Net-(IC22-SW)") (class "Default")
      (node (ref "IC22") (pin "9") (pinfunction "SW_9") (pintype "output"))
      (node (ref "L4") (pin "1") (pinfunction "1_1") (pintype "passive"))
    )
    (net (code "30") (name "Net-(LD1-A)") (class "Default")
      (node (ref "LD1") (pin "2") (pinfunction "A_2") (pintype "passive"))
      (node (ref "R5") (pin "1") (pinfunction "1_1") (pintype "passive"))
    )
    (net (code "31") (name "Net-(LD3-A)") (class "Default")
      (node (ref "LD3") (pin "2") (pinfunction "A_2") (pintype "passive"))
      (node (ref "R33") (pin "1") (pinfunction "1_1") (pintype "passive"))
    )
    (net (code "32") (name "Net-(LD4-A)") (class "Default")
      (node (ref "LD4") (pin "2") (pinfunction "A_2") (pintype "passive"))
      (node (ref "R115") (pin "1") (pinfunction "1_1") (pintype "passive"))
    )
    (net (code "33") (name "Net-(LD7B-A)") (class "Default")
      (node (ref "LD7") (pin "4") (pinfunction "A_4") (pintype "passive"))
      (node (ref "R143") (pin "1") (pinfunction "1_1") (pintype "passive"))
    )
    (net (code "34") (name "Net-(LD9-A)") (class "Default")
      (node (ref "LD9") (pin "2") (pinfunction "A_2") (pintype "passive"))
      (node (ref "R139") (pin "1") (pinfunction "1_1") (pintype "passive"))
    )
    (net (code "35") (name "Net-(LD10-A)") (class "Default")
      (node (ref "LD10") (pin "2") (pinfunction "A_2") (pintype "passive"))
      (node (ref "R116") (pin "1") (pinfunction "1_1") (pintype "passive"))
    )
    (net (code "36") (name "Net-(R84-Pad2)") (class "Default")
      (node (ref "R84") (pin "2") (pinfunction "2_2") (pintype "passive"))
      (node (ref "R87") (pin "1") (pinfunction "1_1") (pintype "passive"))
    )
    (net (code "37") (name "P1V8A") (class "Default")
      (node (ref "C169") (pin "2") (pinfunction "2_2") (pintype "passive"))
      (node (ref "IC18") (pin "1") (pinfunction "OUT_1") (pintype "power_in"))
      (node (ref "IC18") (pin "18") (pinfunction "OUT_18") (pintype "power_in"))
      (node (ref "IC18") (pin "19") (pinfunction "OUT_19") (pintype "power_in"))
      (node (ref "IC18") (pin "20") (pinfunction "OUT_20") (pintype "power_in"))
      (node (ref "R129") (pin "2") (pinfunction "2_2") (pintype "passive"))
      (node (ref "TP10") (pin "1") (pinfunction "1_1") (pintype "bidirectional"))
    )
    (net (code "38") (name "P2V0") (class "Default")
      (node (ref "C163") (pin "2") (pinfunction "2_2") (pintype "passive"))
      (node (ref "C167") (pin "1") (pinfunction "1_1") (pintype "passive"))
      (node (ref "C76") (pin "1") (pinfunction "1_1") (pintype "passive"))
      (node (ref "IC18") (pin "5") (pinfunction "IN_5") (pintype "input"))
      (node (ref "IC18") (pin "6") (pinfunction "IN_6") (pintype "input"))
      (node (ref "IC18") (pin "7") (pinfunction "IN_7") (pintype "input"))
      (node (ref "IC18") (pin "8") (pinfunction "IN_8") (pintype "input"))
      (node (ref "L3") (pin "2") (pinfunction "2_2") (pintype "passive"))
      (node (ref "TP11") (pin "1") (pinfunction "1_1") (pintype "bidirectional"))
    )
    (net (code "39") (name "P3V3") (class "Default")
      (node (ref "C166") (pin "2") (pinfunction "2_2") (pintype "passive"))
      (node (ref "IC11") (pin "1") (pinfunction "OUT_1") (pintype "power_in"))
      (node (ref "IC11") (pin "18") (pinfunction "OUT_18") (pintype "power_in"))
      (node (ref "IC11") (pin "19") (pinfunction "OUT_19") (pintype "power_in"))
      (node (ref "IC11") (pin "20") (pinfunction "OUT_20") (pintype "power_in"))
      (node (ref "R115") (pin "2") (pinfunction "2_2") (pintype "passive"))
      (node (ref "R118") (pin "2") (pinfunction "2_2") (pintype "passive"))
      (node (ref "TP12") (pin "1") (pinfunction "1_1") (pintype "bidirectional"))
    )
    (net (code "40") (name "P3V3A") (class "Default")
      (node (ref "C78") (pin "2") (pinfunction "2_2") (pintype "passive"))
      (node (ref "IC7") (pin "1") (pinfunction "OUT_1") (pintype "power_in"))
      (node (ref "IC7") (pin "18") (pinfunction "OUT_18") (pintype "power_in"))
      (node (ref "IC7") (pin "19") (pinfunction "OUT_19") (pintype "power_in"))
      (node (ref "IC7") (pin "20") (pinfunction "OUT_20") (pintype "power_in"))
      (node (ref "R23") (pin "2") (pinfunction "2_2") (pintype "passive"))
      (node (ref "TP13") (pin "1") (pinfunction "1_1") (pintype "bidirectional"))
    )
    (net (code "41") (name "P3V3_MP") (class "Default")
      (node (ref "C48") (pin "2") (pinfunction "2_2") (pintype "passive"))
      (node (ref "IC12") (pin "8") (pinfunction "+VS_8") (pintype "power_in"))
      (node (ref "R116") (pin "2") (pinfunction "2_2") (pintype "passive"))
      (node (ref "R120") (pin "1") (pinfunction "1_1") (pintype "passive"))
      (node (ref "R121") (pin "2") (pinfunction "2_2") (pintype "passive"))
      (node (ref "R122") (pin "2") (pinfunction "2_2") (pintype "passive"))
      (node (ref "R143") (pin "2") (pinfunction "2_2") (pintype "passive"))
      (node (ref "TP14") (pin "1") (pinfunction "1_1") (pintype "bidirectional"))
    )
    (net (code "42") (name "P3V6") (class "Default")
      (node (ref "C160") (pin "1") (pinfunction "1_1") (pintype "passive"))
      (node (ref "C63") (pin "1") (pinfunction "1_1") (pintype "passive"))
      (node (ref "C74") (pin "1") (pinfunction "1_1") (pintype "passive"))
      (node (ref "C75") (pin "2") (pinfunction "2_2") (pintype "passive"))
      (node (ref "C77") (pin "2") (pinfunction "2_2") (pintype "passive"))
      (node (ref "IC11") (pin "5") (pinfunction "IN_5") (pintype "input"))
      (node (ref "IC11") (pin "6") (pinfunction "IN_6") (pintype "input"))
      (node (ref "IC11") (pin "7") (pinfunction "IN_7") (pintype "input"))
      (node (ref "IC11") (pin "8") (pinfunction "IN_8") (pintype "input"))
      (node (ref "IC7") (pin "10") (pinfunction "BIAS_10") (pintype "input"))
      (node (ref "IC7") (pin "11") (pinfunction "EN_11") (pintype "input"))
      (node (ref "IC7") (pin "5") (pinfunction "IN_5") (pintype "input"))
      (node (ref "IC7") (pin "6") (pinfunction "IN_6") (pintype "input"))
      (node (ref "IC7") (pin "7") (pinfunction "IN_7") (pintype "input"))
      (node (ref "IC7") (pin "8") (pinfunction "IN_8") (pintype "input"))
      (node (ref "L2") (pin "2") (pinfunction "2_2") (pintype "passive"))
      (node (ref "R5") (pin "2") (pinfunction "2_2") (pintype "passive"))
      (node (ref "TP15") (pin "1") (pinfunction "1_1") (pintype "bidirectional"))
    )
    (net (code "43") (name "P5V0A") (class "Default")
      (node (ref "C165") (pin "2") (pinfunction "2_2") (pintype "passive"))
      (node (ref "C168") (pin "2") (pinfunction "2_2") (pintype "passive"))
      (node (ref "C170") (pin "2") (pinfunction "2_2") (pintype "passive"))
      (node (ref "C173") (pin "2") (pinfunction "2_2") (pintype "passive"))
      (node (ref "C79") (pin "1") (pinfunction "1_1") (pintype "passive"))
      (node (ref "IC11") (pin "10") (pinfunction "BIAS_10") (pintype "input"))
      (node (ref "IC11") (pin "11") (pinfunction "EN_11") (pintype "input"))
      (node (ref "IC18") (pin "10") (pinfunction "BIAS_10") (pintype "input"))
      (node (ref "IC18") (pin "11") (pinfunction "EN_11") (pintype "input"))
      (node (ref "IC20") (pin "5") (pinfunction "OUT_5") (pintype "power_in"))
      (node (ref "R131") (pin "2") (pinfunction "2_2") (pintype "passive"))
      (node (ref "R139") (pin "2") (pinfunction "2_2") (pintype "passive"))
      (node (ref "TP16") (pin "1") (pinfunction "1_1") (pintype "bidirectional"))
    )
    (net (code "44") (name "P7V0A") (class "Default")
      (node (ref "C155") (pin "1") (pinfunction "1_1") (pintype "passive"))
      (node (ref "C175") (pin "2") (pinfunction "2_2") (pintype "passive"))
      (node (ref "C177") (pin "2") (pinfunction "2_2") (pintype "passive"))
      (node (ref "IC21") (pin "1") (pinfunction "OUT_1") (pintype "power_in"))
      (node (ref "R133") (pin "2") (pinfunction "2_2") (pintype "passive"))
      (node (ref "TP17") (pin "1") (pinfunction "1_1") (pintype "bidirectional"))
    )
    (net (code "45") (name "P7V5") (class "Default")
      (node (ref "C178") (pin "2") (pinfunction "2_2") (pintype "passive"))
      (node (ref "C179") (pin "2") (pinfunction "2_2") (pintype "passive"))
      (node (ref "IC22") (pin "10") (pinfunction "VOS_10") (pintype "input"))
      (node (ref "IC22") (pin "8") (pinfunction "SLEEP_8") (pintype "input"))
      (node (ref "L4") (pin "2") (pinfunction "2_2") (pintype "passive"))
      (node (ref "L5") (pin "1") (pinfunction "1_1") (pintype "passive"))
      (node (ref "R134") (pin "2") (pinfunction "2_2") (pintype "passive"))
      (node (ref "R53") (pin "2") (pinfunction "2_2") (pintype "passive"))
    )
    (net (code "46") (name "P7V5A") (class "Default")
      (node (ref "C156") (pin "1") (pinfunction "1_1") (pintype "passive"))
      (node (ref "C171") (pin "2") (pinfunction "2_2") (pintype "passive"))
      (node (ref "C174") (pin "2") (pinfunction "2_2") (pintype "passive"))
      (node (ref "C183") (pin "2") (pinfunction "2_2") (pintype "passive"))
      (node (ref "IC20") (pin "1") (pinfunction "IN_1") (pintype "input"))
      (node (ref "IC21") (pin "5") (pinfunction "~{SHDN}_5") (pintype "input"))
      (node (ref "IC21") (pin "8") (pinfunction "IN_8") (pintype "input"))
      (node (ref "L5") (pin "2") (pinfunction "2_2") (pintype "passive"))
    )
    (net (code "47") (name "P12V0") (class "Default")
      (node (ref "C181") (pin "2") (pinfunction "2_2") (pintype "passive"))
      (node (ref "C182") (pin "2") (pinfunction "2_2") (pintype "passive"))
      (node (ref "C64") (pin "2") (pinfunction "2_2") (pintype "passive"))
      (node (ref "C70") (pin "2") (pinfunction "2_2") (pintype "passive"))
      (node (ref "IC15") (pin "A2") (pinfunction "VIN_1_A2") (pintype "power_in"))
      (node (ref "IC15") (pin "B3") (pinfunction "VIN_2_B3") (pintype "power_in"))
      (node (ref "IC15") (pin "D3") (pinfunction "VIN_3_D3") (pintype "power_in"))
      (node (ref "IC15") (pin "E2") (pinfunction "VIN_4_E2") (pintype "power_in"))
      (node (ref "IC22") (pin "2") (pinfunction "VIN_2") (pintype "input"))
      (node (ref "IC22") (pin "3") (pinfunction "EN_3") (pintype "input"))
      (node (ref "R33") (pin "2") (pinfunction "2_2") (pintype "passive"))
      (node (ref "TP18") (pin "1") (pinfunction "1_1") (pintype "bidirectional"))
    )
    (net (code "48") (name "unconnected-(IC7-NC-Pad2)") (class "Default")
      (node (ref "IC7") (pin "2") (pinfunction "NC_2") (pintype "passive+no_connect"))
    )
    (net (code "49") (name "unconnected-(IC7-NC-Pad3)") (class "Default")
      (node (ref "IC7") (pin "3") (pinfunction "NC_3") (pintype "passive+no_connect"))
    )
    (net (code "50") (name "unconnected-(IC7-NC-Pad4)") (class "Default")
      (node (ref "IC7") (pin "4") (pinfunction "NC_4") (pintype "passive+no_connect"))
    )
    (net (code "51") (name "unconnected-(IC7-NC-Pad13)") (class "Default")
      (node (ref "IC7") (pin "13") (pinfunction "NC_13") (pintype "passive+no_connect"))
    )
    (net (code "52") (name "unconnected-(IC7-NC-Pad14)") (class "Default")
      (node (ref "IC7") (pin "14") (pinfunction "NC_14") (pintype "passive+no_connect"))
    )
    (net (code "53") (name "unconnected-(IC7-NC-Pad17)") (class "Default")
      (node (ref "IC7") (pin "17") (pinfunction "NC_17") (pintype "passive+no_connect"))
    )
    (net (code "54") (name "unconnected-(IC7-SS-Pad15)") (class "Default")
      (node (ref "IC7") (pin "15") (pinfunction "SS_15") (pintype "output+no_connect"))
    )
    (net (code "55") (name "unconnected-(IC11-NC-Pad2)") (class "Default")
      (node (ref "IC11") (pin "2") (pinfunction "NC_2") (pintype "passive+no_connect"))
    )
    (net (code "56") (name "unconnected-(IC11-NC-Pad3)") (class "Default")
      (node (ref "IC11") (pin "3") (pinfunction "NC_3") (pintype "passive+no_connect"))
    )
    (net (code "57") (name "unconnected-(IC11-NC-Pad4)") (class "Default")
      (node (ref "IC11") (pin "4") (pinfunction "NC_4") (pintype "passive+no_connect"))
    )
    (net (code "58") (name "unconnected-(IC11-NC-Pad13)") (class "Default")
      (node (ref "IC11") (pin "13") (pinfunction "NC_13") (pintype "passive+no_connect"))
    )
    (net (code "59") (name "unconnected-(IC11-NC-Pad14)") (class "Default")
      (node (ref "IC11") (pin "14") (pinfunction "NC_14") (pintype "passive+no_connect"))
    )
    (net (code "60") (name "unconnected-(IC11-NC-Pad17)") (class "Default")
      (node (ref "IC11") (pin "17") (pinfunction "NC_17") (pintype "passive+no_connect"))
    )
    (net (code "61") (name "unconnected-(IC11-SS-Pad15)") (class "Default")
      (node (ref "IC11") (pin "15") (pinfunction "SS_15") (pintype "output+no_connect"))
    )
    (net (code "62") (name "unconnected-(IC18-NC-Pad2)") (class "Default")
      (node (ref "IC18") (pin "2") (pinfunction "NC_2") (pintype "passive+no_connect"))
    )
    (net (code "63") (name "unconnected-(IC18-NC-Pad3)") (class "Default")
      (node (ref "IC18") (pin "3") (pinfunction "NC_3") (pintype "passive+no_connect"))
    )
    (net (code "64") (name "unconnected-(IC18-NC-Pad4)") (class "Default")
      (node (ref "IC18") (pin "4") (pinfunction "NC_4") (pintype "passive+no_connect"))
    )
    (net (code "65") (name "unconnected-(IC18-NC-Pad13)") (class "Default")
      (node (ref "IC18") (pin "13") (pinfunction "NC_13") (pintype "passive+no_connect"))
    )
    (net (code "66") (name "unconnected-(IC18-NC-Pad14)") (class "Default")
      (node (ref "IC18") (pin "14") (pinfunction "NC_14") (pintype "passive+no_connect"))
    )
    (net (code "67") (name "unconnected-(IC18-NC-Pad17)") (class "Default")
      (node (ref "IC18") (pin "17") (pinfunction "NC_17") (pintype "passive+no_connect"))
    )
    (net (code "68") (name "unconnected-(IC18-SS-Pad15)") (class "Default")
      (node (ref "IC18") (pin "15") (pinfunction "SS_15") (pintype "output+no_connect"))
    )
    (net (code "69") (name "unconnected-(IC22-NC-Pad4)") (class "Default")
      (node (ref "IC22") (pin "4") (pinfunction "NC_4") (pintype "passive"))
    )
  )
)
